# Stereo_VU_Meter_v2.net
KiCad netlist of a schematic drawn in EAGLE
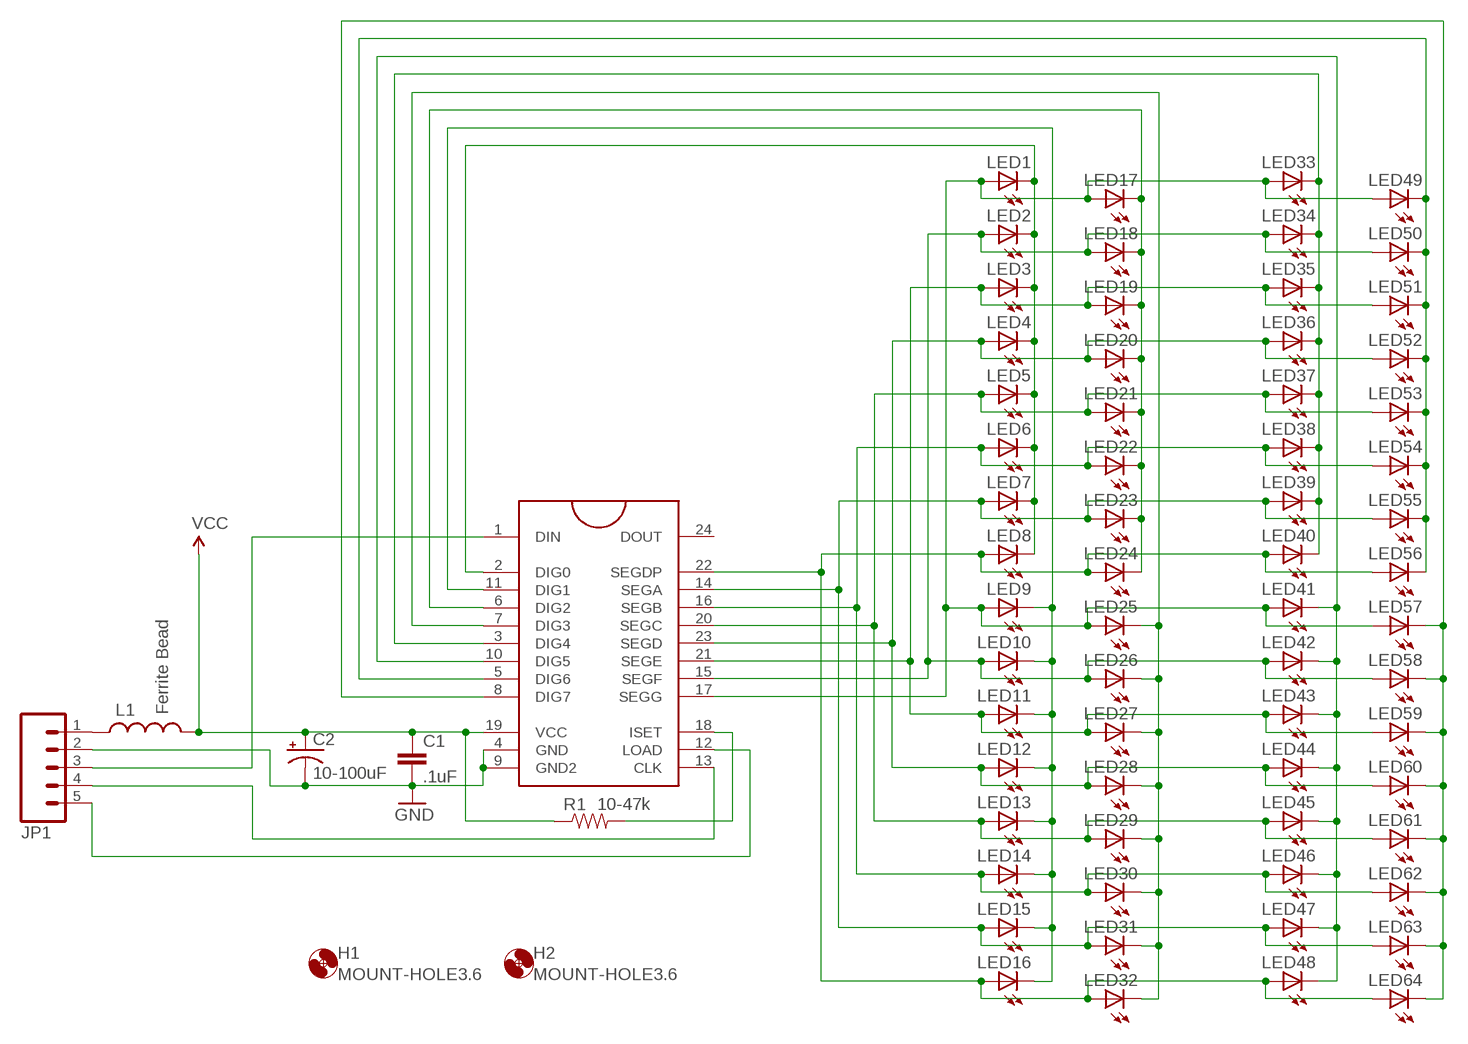
[diagram p0: schematic, sheet 1]

(export (version "E")
  (design (tool "Eeschema 10.0.6"))
  (components
    (comp (ref "C1")
      (value ".1uF")
      (footprint "eagle-import:CAP-PTH-SMALLEZ")
      (libsource (lib "eagle-import") (part "CAPEZ"))
    )
    (comp (ref "C2")
      (value "10-100uF")
      (footprint "eagle-import:CPOL-RADIAL-10UF-25V")
      (libsource (lib "eagle-import") (part "CAP_POLPTH2"))
    )
    (comp (ref "H1")
      (value "MOUNT-HOLE3.6")
      (footprint "eagle-import:3,6")
      (libsource (lib "eagle-import") (part "MOUNT-HOLE3.6"))
    )
    (comp (ref "H2")
      (value "MOUNT-HOLE3.6")
      (footprint "eagle-import:3,6")
      (libsource (lib "eagle-import") (part "MOUNT-HOLE3.6"))
    )
    (comp (ref "JP1")
      (value "M05PTH")
      (footprint "eagle-import:1X05")
      (libsource (lib "eagle-import") (part "M05PTH"))
    )
    (comp (ref "L1")
      (value "Ferrite Bead")
      (footprint "eagle-import:AXIAL-0.3")
      (libsource (lib "eagle-import") (part "FERRITE_BEAD"))
    )
    (comp (ref "LED1")
      (value "LED3MM")
      (footprint "eagle-import:LED3MM")
      (libsource (lib "eagle-import") (part "LED3MM"))
    )
    (comp (ref "LED2")
      (value "LED3MM")
      (footprint "eagle-import:LED3MM")
      (libsource (lib "eagle-import") (part "LED3MM"))
    )
    (comp (ref "LED3")
      (value "LED3MM")
      (footprint "eagle-import:LED3MM")
      (libsource (lib "eagle-import") (part "LED3MM"))
    )
    (comp (ref "LED4")
      (value "LED3MM")
      (footprint "eagle-import:LED3MM")
      (libsource (lib "eagle-import") (part "LED3MM"))
    )
    (comp (ref "LED5")
      (value "LED3MM")
      (footprint "eagle-import:LED3MM")
      (libsource (lib "eagle-import") (part "LED3MM"))
    )
    (comp (ref "LED6")
      (value "LED3MM")
      (footprint "eagle-import:LED3MM")
      (libsource (lib "eagle-import") (part "LED3MM"))
    )
    (comp (ref "LED7")
      (value "LED3MM")
      (footprint "eagle-import:LED3MM")
      (libsource (lib "eagle-import") (part "LED3MM"))
    )
    (comp (ref "LED8")
      (value "LED3MM")
      (footprint "eagle-import:LED3MM")
      (libsource (lib "eagle-import") (part "LED3MM"))
    )
    (comp (ref "LED9")
      (value "LED3MM")
      (footprint "eagle-import:LED3MM")
      (libsource (lib "eagle-import") (part "LED3MM"))
    )
    (comp (ref "LED10")
      (value "LED3MM")
      (footprint "eagle-import:LED3MM")
      (libsource (lib "eagle-import") (part "LED3MM"))
    )
    (comp (ref "LED11")
      (value "LED3MM")
      (footprint "eagle-import:LED3MM")
      (libsource (lib "eagle-import") (part "LED3MM"))
    )
    (comp (ref "LED12")
      (value "LED3MM")
      (footprint "eagle-import:LED3MM")
      (libsource (lib "eagle-import") (part "LED3MM"))
    )
    (comp (ref "LED13")
      (value "LED3MM")
      (footprint "eagle-import:LED3MM")
      (libsource (lib "eagle-import") (part "LED3MM"))
    )
    (comp (ref "LED14")
      (value "LED3MM")
      (footprint "eagle-import:LED3MM")
      (libsource (lib "eagle-import") (part "LED3MM"))
    )
    (comp (ref "LED15")
      (value "LED3MM")
      (footprint "eagle-import:LED3MM")
      (libsource (lib "eagle-import") (part "LED3MM"))
    )
    (comp (ref "LED16")
      (value "LED3MM")
      (footprint "eagle-import:LED3MM")
      (libsource (lib "eagle-import") (part "LED3MM"))
    )
    (comp (ref "LED17")
      (value "LED3MM")
      (footprint "eagle-import:LED3MM")
      (libsource (lib "eagle-import") (part "LED3MM"))
    )
    (comp (ref "LED18")
      (value "LED3MM")
      (footprint "eagle-import:LED3MM")
      (libsource (lib "eagle-import") (part "LED3MM"))
    )
    (comp (ref "LED19")
      (value "LED3MM")
      (footprint "eagle-import:LED3MM")
      (libsource (lib "eagle-import") (part "LED3MM"))
    )
    (comp (ref "LED20")
      (value "LED3MM")
      (footprint "eagle-import:LED3MM")
      (libsource (lib "eagle-import") (part "LED3MM"))
    )
    (comp (ref "LED21")
      (value "LED3MM")
      (footprint "eagle-import:LED3MM")
      (libsource (lib "eagle-import") (part "LED3MM"))
    )
    (comp (ref "LED22")
      (value "LED3MM")
      (footprint "eagle-import:LED3MM")
      (libsource (lib "eagle-import") (part "LED3MM"))
    )
    (comp (ref "LED23")
      (value "LED3MM")
      (footprint "eagle-import:LED3MM")
      (libsource (lib "eagle-import") (part "LED3MM"))
    )
    (comp (ref "LED24")
      (value "LED3MM")
      (footprint "eagle-import:LED3MM")
      (libsource (lib "eagle-import") (part "LED3MM"))
    )
    (comp (ref "LED25")
      (value "LED3MM")
      (footprint "eagle-import:LED3MM")
      (libsource (lib "eagle-import") (part "LED3MM"))
    )
    (comp (ref "LED26")
      (value "LED3MM")
      (footprint "eagle-import:LED3MM")
      (libsource (lib "eagle-import") (part "LED3MM"))
    )
    (comp (ref "LED27")
      (value "LED3MM")
      (footprint "eagle-import:LED3MM")
      (libsource (lib "eagle-import") (part "LED3MM"))
    )
    (comp (ref "LED28")
      (value "LED3MM")
      (footprint "eagle-import:LED3MM")
      (libsource (lib "eagle-import") (part "LED3MM"))
    )
    (comp (ref "LED29")
      (value "LED3MM")
      (footprint "eagle-import:LED3MM")
      (libsource (lib "eagle-import") (part "LED3MM"))
    )
    (comp (ref "LED30")
      (value "LED3MM")
      (footprint "eagle-import:LED3MM")
      (libsource (lib "eagle-import") (part "LED3MM"))
    )
    (comp (ref "LED31")
      (value "LED3MM")
      (footprint "eagle-import:LED3MM")
      (libsource (lib "eagle-import") (part "LED3MM"))
    )
    (comp (ref "LED32")
      (value "LED3MM")
      (footprint "eagle-import:LED3MM")
      (libsource (lib "eagle-import") (part "LED3MM"))
    )
    (comp (ref "LED33")
      (value "LED3MM")
      (footprint "eagle-import:LED3MM")
      (libsource (lib "eagle-import") (part "LED3MM"))
    )
    (comp (ref "LED34")
      (value "LED3MM")
      (footprint "eagle-import:LED3MM")
      (libsource (lib "eagle-import") (part "LED3MM"))
    )
    (comp (ref "LED35")
      (value "LED3MM")
      (footprint "eagle-import:LED3MM")
      (libsource (lib "eagle-import") (part "LED3MM"))
    )
    (comp (ref "LED36")
      (value "LED3MM")
      (footprint "eagle-import:LED3MM")
      (libsource (lib "eagle-import") (part "LED3MM"))
    )
    (comp (ref "LED37")
      (value "LED3MM")
      (footprint "eagle-import:LED3MM")
      (libsource (lib "eagle-import") (part "LED3MM"))
    )
    (comp (ref "LED38")
      (value "LED3MM")
      (footprint "eagle-import:LED3MM")
      (libsource (lib "eagle-import") (part "LED3MM"))
    )
    (comp (ref "LED39")
      (value "LED3MM")
      (footprint "eagle-import:LED3MM")
      (libsource (lib "eagle-import") (part "LED3MM"))
    )
    (comp (ref "LED40")
      (value "LED3MM")
      (footprint "eagle-import:LED3MM")
      (libsource (lib "eagle-import") (part "LED3MM"))
    )
    (comp (ref "LED41")
      (value "LED3MM")
      (footprint "eagle-import:LED3MM")
      (libsource (lib "eagle-import") (part "LED3MM"))
    )
    (comp (ref "LED42")
      (value "LED3MM")
      (footprint "eagle-import:LED3MM")
      (libsource (lib "eagle-import") (part "LED3MM"))
    )
    (comp (ref "LED43")
      (value "LED3MM")
      (footprint "eagle-import:LED3MM")
      (libsource (lib "eagle-import") (part "LED3MM"))
    )
    (comp (ref "LED44")
      (value "LED3MM")
      (footprint "eagle-import:LED3MM")
      (libsource (lib "eagle-import") (part "LED3MM"))
    )
    (comp (ref "LED45")
      (value "LED3MM")
      (footprint "eagle-import:LED3MM")
      (libsource (lib "eagle-import") (part "LED3MM"))
    )
    (comp (ref "LED46")
      (value "LED3MM")
      (footprint "eagle-import:LED3MM")
      (libsource (lib "eagle-import") (part "LED3MM"))
    )
    (comp (ref "LED47")
      (value "LED3MM")
      (footprint "eagle-import:LED3MM")
      (libsource (lib "eagle-import") (part "LED3MM"))
    )
    (comp (ref "LED48")
      (value "LED3MM")
      (footprint "eagle-import:LED3MM")
      (libsource (lib "eagle-import") (part "LED3MM"))
    )
    (comp (ref "LED49")
      (value "LED3MM")
      (footprint "eagle-import:LED3MM")
      (libsource (lib "eagle-import") (part "LED3MM"))
    )
    (comp (ref "LED50")
      (value "LED3MM")
      (footprint "eagle-import:LED3MM")
      (libsource (lib "eagle-import") (part "LED3MM"))
    )
    (comp (ref "LED51")
      (value "LED3MM")
      (footprint "eagle-import:LED3MM")
      (libsource (lib "eagle-import") (part "LED3MM"))
    )
    (comp (ref "LED52")
      (value "LED3MM")
      (footprint "eagle-import:LED3MM")
      (libsource (lib "eagle-import") (part "LED3MM"))
    )
    (comp (ref "LED53")
      (value "LED3MM")
      (footprint "eagle-import:LED3MM")
      (libsource (lib "eagle-import") (part "LED3MM"))
    )
    (comp (ref "LED54")
      (value "LED3MM")
      (footprint "eagle-import:LED3MM")
      (libsource (lib "eagle-import") (part "LED3MM"))
    )
    (comp (ref "LED55")
      (value "LED3MM")
      (footprint "eagle-import:LED3MM")
      (libsource (lib "eagle-import") (part "LED3MM"))
    )
    (comp (ref "LED56")
      (value "LED3MM")
      (footprint "eagle-import:LED3MM")
      (libsource (lib "eagle-import") (part "LED3MM"))
    )
    (comp (ref "LED57")
      (value "LED3MM")
      (footprint "eagle-import:LED3MM")
      (libsource (lib "eagle-import") (part "LED3MM"))
    )
    (comp (ref "LED58")
      (value "LED3MM")
      (footprint "eagle-import:LED3MM")
      (libsource (lib "eagle-import") (part "LED3MM"))
    )
    (comp (ref "LED59")
      (value "LED3MM")
      (footprint "eagle-import:LED3MM")
      (libsource (lib "eagle-import") (part "LED3MM"))
    )
    (comp (ref "LED60")
      (value "LED3MM")
      (footprint "eagle-import:LED3MM")
      (libsource (lib "eagle-import") (part "LED3MM"))
    )
    (comp (ref "LED61")
      (value "LED3MM")
      (footprint "eagle-import:LED3MM")
      (libsource (lib "eagle-import") (part "LED3MM"))
    )
    (comp (ref "LED62")
      (value "LED3MM")
      (footprint "eagle-import:LED3MM")
      (libsource (lib "eagle-import") (part "LED3MM"))
    )
    (comp (ref "LED63")
      (value "LED3MM")
      (footprint "eagle-import:LED3MM")
      (libsource (lib "eagle-import") (part "LED3MM"))
    )
    (comp (ref "LED64")
      (value "LED3MM")
      (footprint "eagle-import:LED3MM")
      (libsource (lib "eagle-import") (part "LED3MM"))
    )
    (comp (ref "R1")
      (value "10-47k")
      (footprint "eagle-import:AXIAL-0.3")
      (libsource (lib "eagle-import") (part "RESISTORAXIAL-0.3"))
    )
    (comp (ref "U1")
      (value "MAX7221DIP")
      (footprint "eagle-import:DIL24")
      (libsource (lib "eagle-import") (part "MAX7221DIP"))
    )
  )
  (nets
    (net (code "1") (name "GND") (class "Default")
      (node (ref "C1") (pin "2") (pinfunction "2_2") (pintype "passive"))
      (node (ref "C2") (pin "2") (pinfunction "-_2") (pintype "passive"))
      (node (ref "JP1") (pin "2") (pinfunction "2_2") (pintype "passive"))
      (node (ref "U1") (pin "4") (pinfunction "GND_4") (pintype "bidirectional"))
      (node (ref "U1") (pin "9") (pinfunction "GND2_9") (pintype "bidirectional"))
    )
    (net (code "2") (name "Net-(L1-1)") (class "Default")
      (node (ref "JP1") (pin "1") (pinfunction "1_1") (pintype "passive"))
      (node (ref "L1") (pin "P$1") (pinfunction "1_P$1") (pintype "passive"))
    )
    (net (code "3") (name "Net-(LED1-C)") (class "Default")
      (node (ref "LED1") (pin "K") (pinfunction "C_K") (pintype "passive"))
      (node (ref "LED2") (pin "K") (pinfunction "C_K") (pintype "passive"))
      (node (ref "LED3") (pin "K") (pinfunction "C_K") (pintype "passive"))
      (node (ref "LED4") (pin "K") (pinfunction "C_K") (pintype "passive"))
      (node (ref "LED5") (pin "K") (pinfunction "C_K") (pintype "passive"))
      (node (ref "LED6") (pin "K") (pinfunction "C_K") (pintype "passive"))
      (node (ref "LED7") (pin "K") (pinfunction "C_K") (pintype "passive"))
      (node (ref "LED8") (pin "K") (pinfunction "C_K") (pintype "passive"))
      (node (ref "U1") (pin "2") (pinfunction "DIG0_2") (pintype "bidirectional"))
    )
    (net (code "4") (name "Net-(LED10-C)") (class "Default")
      (node (ref "LED10") (pin "K") (pinfunction "C_K") (pintype "passive"))
      (node (ref "LED11") (pin "K") (pinfunction "C_K") (pintype "passive"))
      (node (ref "LED12") (pin "K") (pinfunction "C_K") (pintype "passive"))
      (node (ref "LED13") (pin "K") (pinfunction "C_K") (pintype "passive"))
      (node (ref "LED14") (pin "K") (pinfunction "C_K") (pintype "passive"))
      (node (ref "LED15") (pin "K") (pinfunction "C_K") (pintype "passive"))
      (node (ref "LED16") (pin "K") (pinfunction "C_K") (pintype "passive"))
      (node (ref "LED9") (pin "K") (pinfunction "C_K") (pintype "passive"))
      (node (ref "U1") (pin "11") (pinfunction "DIG1_11") (pintype "bidirectional"))
    )
    (net (code "5") (name "Net-(LED17-C)") (class "Default")
      (node (ref "LED17") (pin "K") (pinfunction "C_K") (pintype "passive"))
      (node (ref "LED18") (pin "K") (pinfunction "C_K") (pintype "passive"))
      (node (ref "LED19") (pin "K") (pinfunction "C_K") (pintype "passive"))
      (node (ref "LED20") (pin "K") (pinfunction "C_K") (pintype "passive"))
      (node (ref "LED21") (pin "K") (pinfunction "C_K") (pintype "passive"))
      (node (ref "LED22") (pin "K") (pinfunction "C_K") (pintype "passive"))
      (node (ref "LED23") (pin "K") (pinfunction "C_K") (pintype "passive"))
      (node (ref "LED24") (pin "K") (pinfunction "C_K") (pintype "passive"))
      (node (ref "U1") (pin "6") (pinfunction "DIG2_6") (pintype "bidirectional"))
    )
    (net (code "6") (name "Net-(LED25-C)") (class "Default")
      (node (ref "LED25") (pin "K") (pinfunction "C_K") (pintype "passive"))
      (node (ref "LED26") (pin "K") (pinfunction "C_K") (pintype "passive"))
      (node (ref "LED27") (pin "K") (pinfunction "C_K") (pintype "passive"))
      (node (ref "LED28") (pin "K") (pinfunction "C_K") (pintype "passive"))
      (node (ref "LED29") (pin "K") (pinfunction "C_K") (pintype "passive"))
      (node (ref "LED30") (pin "K") (pinfunction "C_K") (pintype "passive"))
      (node (ref "LED31") (pin "K") (pinfunction "C_K") (pintype "passive"))
      (node (ref "LED32") (pin "K") (pinfunction "C_K") (pintype "passive"))
      (node (ref "U1") (pin "7") (pinfunction "DIG3_7") (pintype "bidirectional"))
    )
    (net (code "7") (name "Net-(LED33-C)") (class "Default")
      (node (ref "LED33") (pin "K") (pinfunction "C_K") (pintype "passive"))
      (node (ref "LED34") (pin "K") (pinfunction "C_K") (pintype "passive"))
      (node (ref "LED35") (pin "K") (pinfunction "C_K") (pintype "passive"))
      (node (ref "LED36") (pin "K") (pinfunction "C_K") (pintype "passive"))
      (node (ref "LED37") (pin "K") (pinfunction "C_K") (pintype "passive"))
      (node (ref "LED38") (pin "K") (pinfunction "C_K") (pintype "passive"))
      (node (ref "LED39") (pin "K") (pinfunction "C_K") (pintype "passive"))
      (node (ref "LED40") (pin "K") (pinfunction "C_K") (pintype "passive"))
      (node (ref "U1") (pin "3") (pinfunction "DIG4_3") (pintype "bidirectional"))
    )
    (net (code "8") (name "Net-(LED41-C)") (class "Default")
      (node (ref "LED41") (pin "K") (pinfunction "C_K") (pintype "passive"))
      (node (ref "LED42") (pin "K") (pinfunction "C_K") (pintype "passive"))
      (node (ref "LED43") (pin "K") (pinfunction "C_K") (pintype "passive"))
      (node (ref "LED44") (pin "K") (pinfunction "C_K") (pintype "passive"))
      (node (ref "LED45") (pin "K") (pinfunction "C_K") (pintype "passive"))
      (node (ref "LED46") (pin "K") (pinfunction "C_K") (pintype "passive"))
      (node (ref "LED47") (pin "K") (pinfunction "C_K") (pintype "passive"))
      (node (ref "LED48") (pin "K") (pinfunction "C_K") (pintype "passive"))
      (node (ref "U1") (pin "10") (pinfunction "DIG5_10") (pintype "bidirectional"))
    )
    (net (code "9") (name "Net-(LED49-C)") (class "Default")
      (node (ref "LED49") (pin "K") (pinfunction "C_K") (pintype "passive"))
      (node (ref "LED50") (pin "K") (pinfunction "C_K") (pintype "passive"))
      (node (ref "LED51") (pin "K") (pinfunction "C_K") (pintype "passive"))
      (node (ref "LED52") (pin "K") (pinfunction "C_K") (pintype "passive"))
      (node (ref "LED53") (pin "K") (pinfunction "C_K") (pintype "passive"))
      (node (ref "LED54") (pin "K") (pinfunction "C_K") (pintype "passive"))
      (node (ref "LED55") (pin "K") (pinfunction "C_K") (pintype "passive"))
      (node (ref "LED56") (pin "K") (pinfunction "C_K") (pintype "passive"))
      (node (ref "U1") (pin "5") (pinfunction "DIG6_5") (pintype "bidirectional"))
    )
    (net (code "10") (name "Net-(LED57-C)") (class "Default")
      (node (ref "LED57") (pin "K") (pinfunction "C_K") (pintype "passive"))
      (node (ref "LED58") (pin "K") (pinfunction "C_K") (pintype "passive"))
      (node (ref "LED59") (pin "K") (pinfunction "C_K") (pintype "passive"))
      (node (ref "LED60") (pin "K") (pinfunction "C_K") (pintype "passive"))
      (node (ref "LED61") (pin "K") (pinfunction "C_K") (pintype "passive"))
      (node (ref "LED62") (pin "K") (pinfunction "C_K") (pintype "passive"))
      (node (ref "LED63") (pin "K") (pinfunction "C_K") (pintype "passive"))
      (node (ref "LED64") (pin "K") (pinfunction "C_K") (pintype "passive"))
      (node (ref "U1") (pin "8") (pinfunction "DIG7_8") (pintype "bidirectional"))
    )
    (net (code "11") (name "Net-(R1-2)") (class "Default")
      (node (ref "R1") (pin "P$2") (pinfunction "2_P$2") (pintype "passive"))
      (node (ref "U1") (pin "18") (pinfunction "ISET_18") (pintype "bidirectional"))
    )
    (net (code "12") (name "Net-(U1-CLK)") (class "Default")
      (node (ref "JP1") (pin "4") (pinfunction "4_4") (pintype "passive"))
      (node (ref "U1") (pin "13") (pinfunction "CLK_13") (pintype "bidirectional"))
    )
    (net (code "13") (name "Net-(U1-DIN)") (class "Default")
      (node (ref "JP1") (pin "3") (pinfunction "3_3") (pintype "passive"))
      (node (ref "U1") (pin "1") (pinfunction "DIN_1") (pintype "bidirectional"))
    )
    (net (code "14") (name "Net-(U1-LOAD)") (class "Default")
      (node (ref "JP1") (pin "5") (pinfunction "5_5") (pintype "passive"))
      (node (ref "U1") (pin "12") (pinfunction "LOAD_12") (pintype "bidirectional"))
    )
    (net (code "15") (name "Net-(U1-SEGA)") (class "Default")
      (node (ref "LED15") (pin "A") (pinfunction "A_A") (pintype "passive"))
      (node (ref "LED23") (pin "A") (pinfunction "A_A") (pintype "passive"))
      (node (ref "LED31") (pin "A") (pinfunction "A_A") (pintype "passive"))
      (node (ref "LED39") (pin "A") (pinfunction "A_A") (pintype "passive"))
      (node (ref "LED47") (pin "A") (pinfunction "A_A") (pintype "passive"))
      (node (ref "LED55") (pin "A") (pinfunction "A_A") (pintype "passive"))
      (node (ref "LED63") (pin "A") (pinfunction "A_A") (pintype "passive"))
      (node (ref "LED7") (pin "A") (pinfunction "A_A") (pintype "passive"))
      (node (ref "U1") (pin "14") (pinfunction "SEGA_14") (pintype "bidirectional"))
    )
    (net (code "16") (name "Net-(U1-SEGB)") (class "Default")
      (node (ref "LED14") (pin "A") (pinfunction "A_A") (pintype "passive"))
      (node (ref "LED22") (pin "A") (pinfunction "A_A") (pintype "passive"))
      (node (ref "LED30") (pin "A") (pinfunction "A_A") (pintype "passive"))
      (node (ref "LED38") (pin "A") (pinfunction "A_A") (pintype "passive"))
      (node (ref "LED46") (pin "A") (pinfunction "A_A") (pintype "passive"))
      (node (ref "LED54") (pin "A") (pinfunction "A_A") (pintype "passive"))
      (node (ref "LED6") (pin "A") (pinfunction "A_A") (pintype "passive"))
      (node (ref "LED62") (pin "A") (pinfunction "A_A") (pintype "passive"))
      (node (ref "U1") (pin "16") (pinfunction "SEGB_16") (pintype "bidirectional"))
    )
    (net (code "17") (name "Net-(U1-SEGC)") (class "Default")
      (node (ref "LED13") (pin "A") (pinfunction "A_A") (pintype "passive"))
      (node (ref "LED21") (pin "A") (pinfunction "A_A") (pintype "passive"))
      (node (ref "LED29") (pin "A") (pinfunction "A_A") (pintype "passive"))
      (node (ref "LED37") (pin "A") (pinfunction "A_A") (pintype "passive"))
      (node (ref "LED45") (pin "A") (pinfunction "A_A") (pintype "passive"))
      (node (ref "LED5") (pin "A") (pinfunction "A_A") (pintype "passive"))
      (node (ref "LED53") (pin "A") (pinfunction "A_A") (pintype "passive"))
      (node (ref "LED61") (pin "A") (pinfunction "A_A") (pintype "passive"))
      (node (ref "U1") (pin "20") (pinfunction "SEGC_20") (pintype "bidirectional"))
    )
    (net (code "18") (name "Net-(U1-SEGD)") (class "Default")
      (node (ref "LED12") (pin "A") (pinfunction "A_A") (pintype "passive"))
      (node (ref "LED20") (pin "A") (pinfunction "A_A") (pintype "passive"))
      (node (ref "LED28") (pin "A") (pinfunction "A_A") (pintype "passive"))
      (node (ref "LED36") (pin "A") (pinfunction "A_A") (pintype "passive"))
      (node (ref "LED4") (pin "A") (pinfunction "A_A") (pintype "passive"))
      (node (ref "LED44") (pin "A") (pinfunction "A_A") (pintype "passive"))
      (node (ref "LED52") (pin "A") (pinfunction "A_A") (pintype "passive"))
      (node (ref "LED60") (pin "A") (pinfunction "A_A") (pintype "passive"))
      (node (ref "U1") (pin "23") (pinfunction "SEGD_23") (pintype "bidirectional"))
    )
    (net (code "19") (name "Net-(U1-SEGDP)") (class "Default")
      (node (ref "LED16") (pin "A") (pinfunction "A_A") (pintype "passive"))
      (node (ref "LED24") (pin "A") (pinfunction "A_A") (pintype "passive"))
      (node (ref "LED32") (pin "A") (pinfunction "A_A") (pintype "passive"))
      (node (ref "LED40") (pin "A") (pinfunction "A_A") (pintype "passive"))
      (node (ref "LED48") (pin "A") (pinfunction "A_A") (pintype "passive"))
      (node (ref "LED56") (pin "A") (pinfunction "A_A") (pintype "passive"))
      (node (ref "LED64") (pin "A") (pinfunction "A_A") (pintype "passive"))
      (node (ref "LED8") (pin "A") (pinfunction "A_A") (pintype "passive"))
      (node (ref "U1") (pin "22") (pinfunction "SEGDP_22") (pintype "bidirectional"))
    )
    (net (code "20") (name "Net-(U1-SEGE)") (class "Default")
      (node (ref "LED11") (pin "A") (pinfunction "A_A") (pintype "passive"))
      (node (ref "LED19") (pin "A") (pinfunction "A_A") (pintype "passive"))
      (node (ref "LED27") (pin "A") (pinfunction "A_A") (pintype "passive"))
      (node (ref "LED3") (pin "A") (pinfunction "A_A") (pintype "passive"))
      (node (ref "LED35") (pin "A") (pinfunction "A_A") (pintype "passive"))
      (node (ref "LED43") (pin "A") (pinfunction "A_A") (pintype "passive"))
      (node (ref "LED51") (pin "A") (pinfunction "A_A") (pintype "passive"))
      (node (ref "LED59") (pin "A") (pinfunction "A_A") (pintype "passive"))
      (node (ref "U1") (pin "21") (pinfunction "SEGE_21") (pintype "bidirectional"))
    )
    (net (code "21") (name "Net-(U1-SEGF)") (class "Default")
      (node (ref "LED10") (pin "A") (pinfunction "A_A") (pintype "passive"))
      (node (ref "LED18") (pin "A") (pinfunction "A_A") (pintype "passive"))
      (node (ref "LED2") (pin "A") (pinfunction "A_A") (pintype "passive"))
      (node (ref "LED26") (pin "A") (pinfunction "A_A") (pintype "passive"))
      (node (ref "LED34") (pin "A") (pinfunction "A_A") (pintype "passive"))
      (node (ref "LED42") (pin "A") (pinfunction "A_A") (pintype "passive"))
      (node (ref "LED50") (pin "A") (pinfunction "A_A") (pintype "passive"))
      (node (ref "LED58") (pin "A") (pinfunction "A_A") (pintype "passive"))
      (node (ref "U1") (pin "15") (pinfunction "SEGF_15") (pintype "bidirectional"))
    )
    (net (code "22") (name "Net-(U1-SEGG)") (class "Default")
      (node (ref "LED1") (pin "A") (pinfunction "A_A") (pintype "passive"))
      (node (ref "LED17") (pin "A") (pinfunction "A_A") (pintype "passive"))
      (node (ref "LED25") (pin "A") (pinfunction "A_A") (pintype "passive"))
      (node (ref "LED33") (pin "A") (pinfunction "A_A") (pintype "passive"))
      (node (ref "LED41") (pin "A") (pinfunction "A_A") (pintype "passive"))
      (node (ref "LED49") (pin "A") (pinfunction "A_A") (pintype "passive"))
      (node (ref "LED57") (pin "A") (pinfunction "A_A") (pintype "passive"))
      (node (ref "LED9") (pin "A") (pinfunction "A_A") (pintype "passive"))
      (node (ref "U1") (pin "17") (pinfunction "SEGG_17") (pintype "bidirectional"))
    )
    (net (code "23") (name "VCC") (class "Default")
      (node (ref "C1") (pin "1") (pinfunction "1_1") (pintype "passive"))
      (node (ref "C2") (pin "1") (pinfunction "+_1") (pintype "passive"))
      (node (ref "L1") (pin "P$2") (pinfunction "2_P$2") (pintype "passive"))
      (node (ref "R1") (pin "P$1") (pinfunction "1_P$1") (pintype "passive"))
      (node (ref "U1") (pin "19") (pinfunction "VCC_19") (pintype "bidirectional"))
    )
    (net (code "24") (name "unconnected-(U1-DOUT-Pad24)") (class "Default")
      (node (ref "U1") (pin "24") (pinfunction "DOUT_24") (pintype "bidirectional"))
    )
  )
)
